# distortion-noise-and-ring-modulator-v1_1.net
KiCad netlist of a schematic drawn in EAGLE
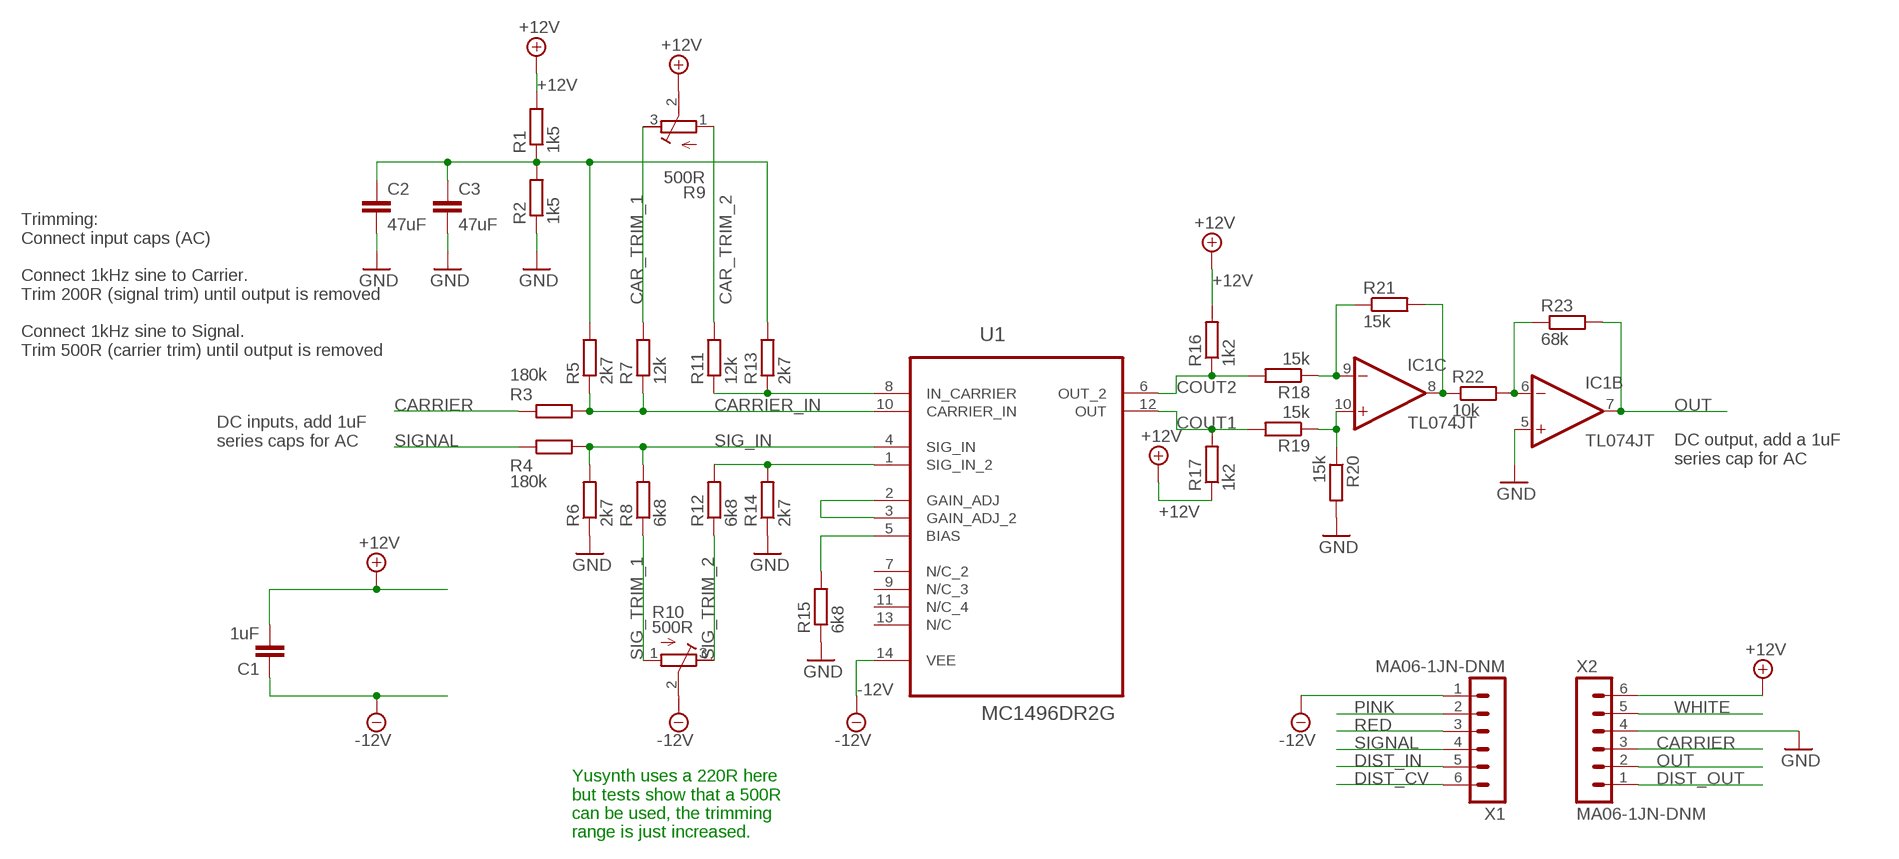
[diagram p0: schematic, sheet 1]
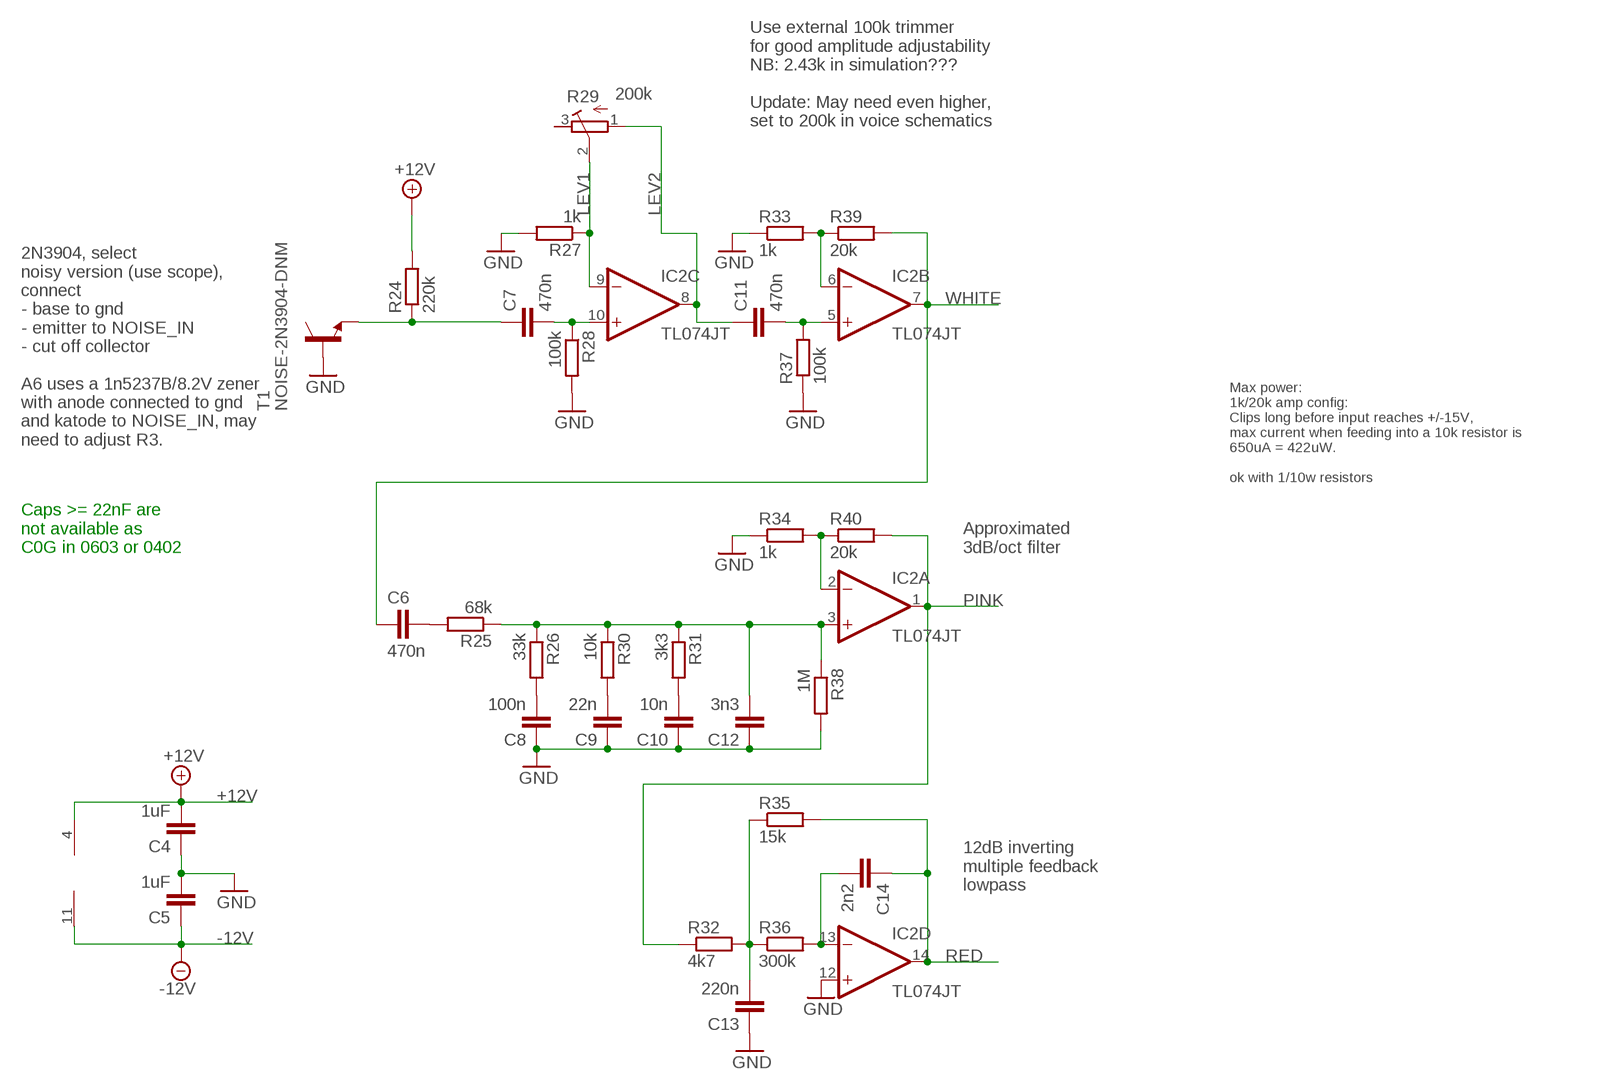
[diagram p1: schematic, sheet 2]
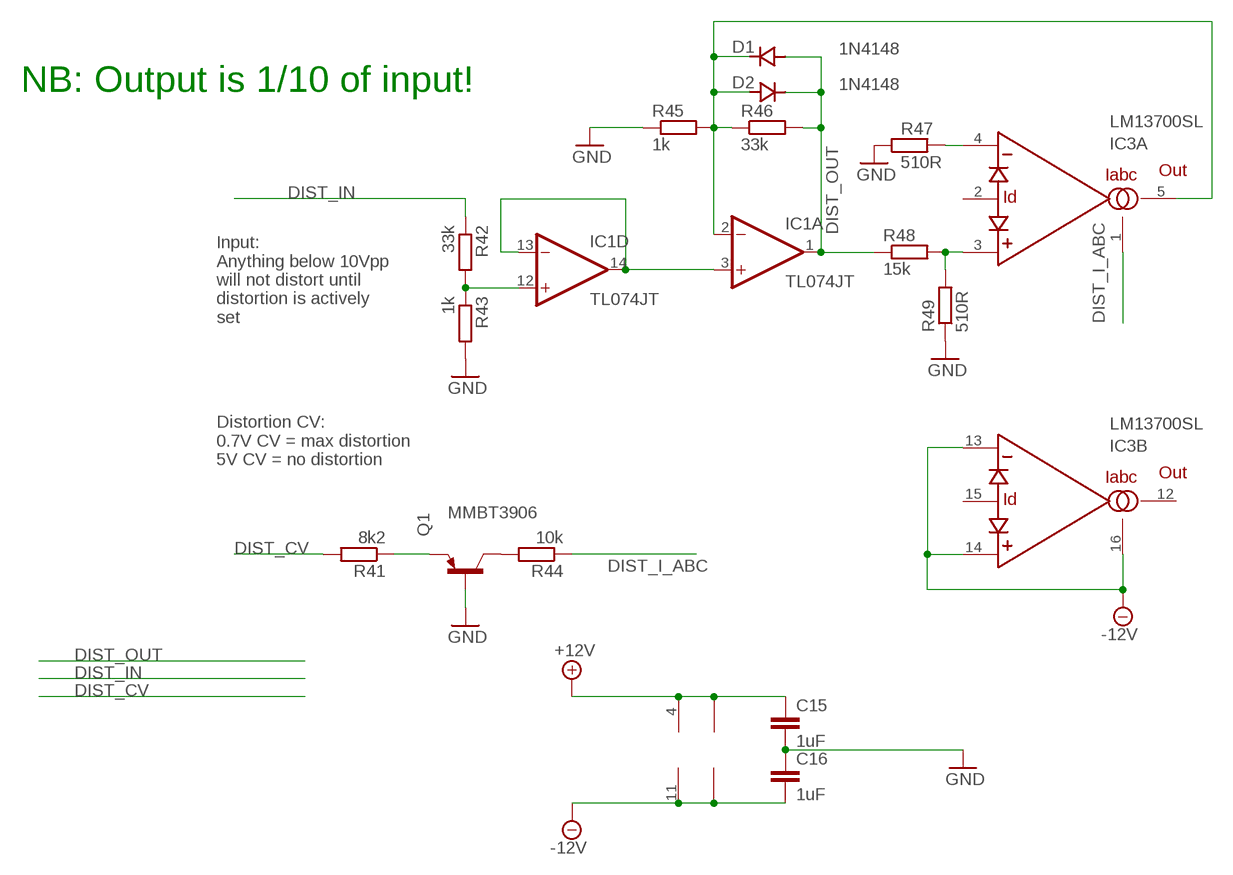
[diagram p2: schematic, sheet 3]

(export (version "E")
  (design (tool "Eeschema 10.0.6"))
  (components
    (comp (ref "C4")
      (value "1uF")
      (footprint "eagle-import:C0402-J")
      (libsource (lib "eagle-import") (part "C-EU-J0402"))
    )
    (comp (ref "C5")
      (value "1uF")
      (footprint "eagle-import:C0402-J")
      (libsource (lib "eagle-import") (part "C-EU-J0402"))
    )
    (comp (ref "C6")
      (value "470n")
      (footprint "eagle-import:C0603-J")
      (libsource (lib "eagle-import") (part "C-EU-J0603"))
    )
    (comp (ref "C7")
      (value "470n")
      (footprint "eagle-import:C0603-J")
      (libsource (lib "eagle-import") (part "C-EU-J0603"))
    )
    (comp (ref "C8")
      (value "100n")
      (footprint "eagle-import:C0402-J")
      (libsource (lib "eagle-import") (part "C-EU-J0402"))
    )
    (comp (ref "C9")
      (value "22n")
      (footprint "eagle-import:C0402-J")
      (libsource (lib "eagle-import") (part "C-EU-J0402"))
    )
    (comp (ref "C10")
      (value "10n")
      (footprint "eagle-import:C0402-J")
      (libsource (lib "eagle-import") (part "C-EU-J0402"))
    )
    (comp (ref "C11")
      (value "470n")
      (footprint "eagle-import:C0603-J")
      (libsource (lib "eagle-import") (part "C-EU-J0603"))
    )
    (comp (ref "C12")
      (value "3n3")
      (footprint "eagle-import:C0603-J")
      (libsource (lib "eagle-import") (part "C-EU-J0603"))
    )
    (comp (ref "C13")
      (value "220n")
      (footprint "eagle-import:C0402-J")
      (libsource (lib "eagle-import") (part "C-EU-J0402"))
    )
    (comp (ref "C14")
      (value "2n2")
      (footprint "eagle-import:C0603-J")
      (libsource (lib "eagle-import") (part "C-EU-J0603"))
    )
    (comp (ref "IC2")
      (value "TL074JT")
      (footprint "eagle-import:TSSOP14J")
      (libsource (lib "eagle-import") (part "TL074JT"))
    )
    (comp (ref "R24")
      (value "220k")
      (footprint "eagle-import:R0603")
      (libsource (lib "eagle-import") (part "R-EU_R0603"))
    )
    (comp (ref "R25")
      (value "68k")
      (footprint "eagle-import:R0603")
      (libsource (lib "eagle-import") (part "R-EU_R0603"))
    )
    (comp (ref "R26")
      (value "33k")
      (footprint "eagle-import:R0402")
      (libsource (lib "eagle-import") (part "R-EU_R0402"))
    )
    (comp (ref "R27")
      (value "1k")
      (footprint "eagle-import:R0402")
      (libsource (lib "eagle-import") (part "R-EU_R0402"))
    )
    (comp (ref "R28")
      (value "100k")
      (footprint "eagle-import:R0402")
      (libsource (lib "eagle-import") (part "R-EU_R0402"))
    )
    (comp (ref "R29")
      (value "200k")
      (footprint "eagle-import:RTRIM3296W")
      (libsource (lib "eagle-import") (part "R-TRIMM3296W"))
    )
    (comp (ref "R30")
      (value "10k")
      (footprint "eagle-import:R0402")
      (libsource (lib "eagle-import") (part "R-EU_R0402"))
    )
    (comp (ref "R31")
      (value "3k3")
      (footprint "eagle-import:R0402")
      (libsource (lib "eagle-import") (part "R-EU_R0402"))
    )
    (comp (ref "R32")
      (value "4k7")
      (footprint "eagle-import:R0402")
      (libsource (lib "eagle-import") (part "R-EU_R0402"))
    )
    (comp (ref "R33")
      (value "1k")
      (footprint "eagle-import:R0402")
      (libsource (lib "eagle-import") (part "R-EU_R0402"))
    )
    (comp (ref "R34")
      (value "1k")
      (footprint "eagle-import:R0402")
      (libsource (lib "eagle-import") (part "R-EU_R0402"))
    )
    (comp (ref "R35")
      (value "15k")
      (footprint "eagle-import:R0402")
      (libsource (lib "eagle-import") (part "R-EU_R0402"))
    )
    (comp (ref "R36")
      (value "300k")
      (footprint "eagle-import:R0603")
      (libsource (lib "eagle-import") (part "R-EU_R0603"))
    )
    (comp (ref "R37")
      (value "100k")
      (footprint "eagle-import:R0402")
      (libsource (lib "eagle-import") (part "R-EU_R0402"))
    )
    (comp (ref "R38")
      (value "1M")
      (footprint "eagle-import:R0402")
      (libsource (lib "eagle-import") (part "R-EU_R0402"))
    )
    (comp (ref "R39")
      (value "20k")
      (footprint "eagle-import:R0402")
      (libsource (lib "eagle-import") (part "R-EU_R0402"))
    )
    (comp (ref "R40")
      (value "20k")
      (footprint "eagle-import:R0402")
      (libsource (lib "eagle-import") (part "R-EU_R0402"))
    )
    (comp (ref "T1")
      (value "NOISE-2N3904-DNM")
      (footprint "eagle-import:NOISE-2N3904-J")
      (libsource (lib "eagle-import") (part "NOISE-2N3904"))
    )
    (comp (ref "C1")
      (value "1uF")
      (footprint "eagle-import:C0402-J")
      (libsource (lib "eagle-import") (part "C-EU-J0402"))
    )
    (comp (ref "C2")
      (value "47uF")
      (footprint "eagle-import:C1206")
      (libsource (lib "eagle-import") (part "C-EUC1206"))
    )
    (comp (ref "C3")
      (value "47uF")
      (footprint "eagle-import:C1206")
      (libsource (lib "eagle-import") (part "C-EUC1206"))
    )
    (comp (ref "IC1")
      (value "TL074JT")
      (footprint "eagle-import:TSSOP14J")
      (libsource (lib "eagle-import") (part "TL074JT"))
    )
    (comp (ref "R1")
      (value "1k5")
      (footprint "eagle-import:R0402")
      (libsource (lib "eagle-import") (part "R-EU_R0402"))
    )
    (comp (ref "R2")
      (value "1k5")
      (footprint "eagle-import:R0402")
      (libsource (lib "eagle-import") (part "R-EU_R0402"))
    )
    (comp (ref "R3")
      (value "180k")
      (footprint "eagle-import:R0402")
      (libsource (lib "eagle-import") (part "R-EU_R0402"))
    )
    (comp (ref "R4")
      (value "180k")
      (footprint "eagle-import:R0402")
      (libsource (lib "eagle-import") (part "R-EU_R0402"))
    )
    (comp (ref "R5")
      (value "2k7")
      (footprint "eagle-import:R0603")
      (libsource (lib "eagle-import") (part "R-EU_R0603"))
    )
    (comp (ref "R6")
      (value "2k7")
      (footprint "eagle-import:R0603")
      (libsource (lib "eagle-import") (part "R-EU_R0603"))
    )
    (comp (ref "R7")
      (value "12k")
      (footprint "eagle-import:R0402")
      (libsource (lib "eagle-import") (part "R-EU_R0402"))
    )
    (comp (ref "R8")
      (value "6k8")
      (footprint "eagle-import:R0603")
      (libsource (lib "eagle-import") (part "R-EU_R0603"))
    )
    (comp (ref "R9")
      (value "500R")
      (footprint "eagle-import:RTRIM3296X")
      (libsource (lib "eagle-import") (part "R-TRIMM3296X"))
    )
    (comp (ref "R10")
      (value "500R")
      (footprint "eagle-import:RTRIM3296X")
      (libsource (lib "eagle-import") (part "R-TRIMM3296X"))
    )
    (comp (ref "R11")
      (value "12k")
      (footprint "eagle-import:R0402")
      (libsource (lib "eagle-import") (part "R-EU_R0402"))
    )
    (comp (ref "R12")
      (value "6k8")
      (footprint "eagle-import:R0603")
      (libsource (lib "eagle-import") (part "R-EU_R0603"))
    )
    (comp (ref "R13")
      (value "2k7")
      (footprint "eagle-import:R0603")
      (libsource (lib "eagle-import") (part "R-EU_R0603"))
    )
    (comp (ref "R14")
      (value "2k7")
      (footprint "eagle-import:R0603")
      (libsource (lib "eagle-import") (part "R-EU_R0603"))
    )
    (comp (ref "R15")
      (value "6k8")
      (footprint "eagle-import:R0603")
      (libsource (lib "eagle-import") (part "R-EU_R0603"))
    )
    (comp (ref "R16")
      (value "1k2")
      (footprint "eagle-import:R0603")
      (libsource (lib "eagle-import") (part "R-EU_R0603"))
    )
    (comp (ref "R17")
      (value "1k2")
      (footprint "eagle-import:R0603")
      (libsource (lib "eagle-import") (part "R-EU_R0603"))
    )
    (comp (ref "R18")
      (value "15k")
      (footprint "eagle-import:R0402")
      (libsource (lib "eagle-import") (part "R-EU_R0402"))
    )
    (comp (ref "R19")
      (value "15k")
      (footprint "eagle-import:R0402")
      (libsource (lib "eagle-import") (part "R-EU_R0402"))
    )
    (comp (ref "R20")
      (value "15k")
      (footprint "eagle-import:R0402")
      (libsource (lib "eagle-import") (part "R-EU_R0402"))
    )
    (comp (ref "R21")
      (value "15k")
      (footprint "eagle-import:R0402")
      (libsource (lib "eagle-import") (part "R-EU_R0402"))
    )
    (comp (ref "R22")
      (value "10k")
      (footprint "eagle-import:R0402")
      (libsource (lib "eagle-import") (part "R-EU_R0402"))
    )
    (comp (ref "R23")
      (value "68k")
      (footprint "eagle-import:R0603")
      (libsource (lib "eagle-import") (part "R-EU_R0603"))
    )
    (comp (ref "U1")
      (value "MC1496DR2G")
      (footprint "eagle-import:SOIC127P600X175-14N")
      (libsource (lib "eagle-import") (part "MC1496DR2G"))
    )
    (comp (ref "X1")
      (value "MA06-1JN-DNM")
      (footprint "eagle-import:MA06N-1J")
      (libsource (lib "eagle-import") (part "MA06-1JN"))
    )
    (comp (ref "X2")
      (value "MA06-1JN-DNM")
      (footprint "eagle-import:MA06N-1J")
      (libsource (lib "eagle-import") (part "MA06-1JN"))
    )
    (comp (ref "C15")
      (value "1uF")
      (footprint "eagle-import:C0402-J")
      (libsource (lib "eagle-import") (part "C-EU-J0402"))
    )
    (comp (ref "C16")
      (value "1uF")
      (footprint "eagle-import:C0402-J")
      (libsource (lib "eagle-import") (part "C-EU-J0402"))
    )
    (comp (ref "D1")
      (value "1N4148")
      (footprint "eagle-import:SOD323J")
      (libsource (lib "eagle-import") (part "1N4148SOD323"))
    )
    (comp (ref "D2")
      (value "1N4148")
      (footprint "eagle-import:SOD323J")
      (libsource (lib "eagle-import") (part "1N4148SOD323"))
    )
    (comp (ref "IC3")
      (value "LM13700SL")
      (footprint "eagle-import:SO16-NARROW-J")
      (libsource (lib "eagle-import") (part "LM13700SL"))
    )
    (comp (ref "Q1")
      (value "MMBT3906")
      (footprint "eagle-import:SOT23-BEC")
      (libsource (lib "eagle-import") (part "MMBT3906SMDLT1"))
    )
    (comp (ref "R41")
      (value "8k2")
      (footprint "eagle-import:R0603")
      (libsource (lib "eagle-import") (part "R-EU_R0603"))
    )
    (comp (ref "R42")
      (value "33k")
      (footprint "eagle-import:R0402")
      (libsource (lib "eagle-import") (part "R-EU_R0402"))
    )
    (comp (ref "R43")
      (value "1k")
      (footprint "eagle-import:R0402")
      (libsource (lib "eagle-import") (part "R-EU_R0402"))
    )
    (comp (ref "R44")
      (value "10k")
      (footprint "eagle-import:R0402")
      (libsource (lib "eagle-import") (part "R-EU_R0402"))
    )
    (comp (ref "R45")
      (value "1k")
      (footprint "eagle-import:R0402")
      (libsource (lib "eagle-import") (part "R-EU_R0402"))
    )
    (comp (ref "R46")
      (value "33k")
      (footprint "eagle-import:R0402")
      (libsource (lib "eagle-import") (part "R-EU_R0402"))
    )
    (comp (ref "R47")
      (value "510R")
      (footprint "eagle-import:R0402")
      (libsource (lib "eagle-import") (part "R-EU_R0402"))
    )
    (comp (ref "R48")
      (value "15k")
      (footprint "eagle-import:R0402")
      (libsource (lib "eagle-import") (part "R-EU_R0402"))
    )
    (comp (ref "R49")
      (value "510R")
      (footprint "eagle-import:R0402")
      (libsource (lib "eagle-import") (part "R-EU_R0402"))
    )
  )
  (nets
    (net (code "1") (name "+12V") (class "Default")
      (node (ref "C1") (pin "2") (pinfunction "2_2") (pintype "passive"))
      (node (ref "C15") (pin "1") (pinfunction "1_1") (pintype "passive"))
      (node (ref "C4") (pin "2") (pinfunction "2_2") (pintype "passive"))
      (node (ref "IC1") (pin "4") (pinfunction "V+_4") (pintype "power_in"))
      (node (ref "IC2") (pin "4") (pinfunction "V+_4") (pintype "power_in"))
      (node (ref "IC3") (pin "11") (pinfunction "V+_11") (pintype "bidirectional"))
      (node (ref "R1") (pin "2") (pinfunction "2_2") (pintype "passive"))
      (node (ref "R16") (pin "2") (pinfunction "2_2") (pintype "passive"))
      (node (ref "R17") (pin "1") (pinfunction "1_1") (pintype "passive"))
      (node (ref "R24") (pin "2") (pinfunction "2_2") (pintype "passive"))
      (node (ref "R9") (pin "2") (pinfunction "S_2") (pintype "passive"))
      (node (ref "X2") (pin "6") (pinfunction "6_6") (pintype "passive"))
    )
    (net (code "2") (name "-12V") (class "Default")
      (node (ref "C1") (pin "1") (pinfunction "1_1") (pintype "passive"))
      (node (ref "C16") (pin "2") (pinfunction "2_2") (pintype "passive"))
      (node (ref "C5") (pin "1") (pinfunction "1_1") (pintype "passive"))
      (node (ref "IC1") (pin "11") (pinfunction "V-_11") (pintype "power_in"))
      (node (ref "IC2") (pin "11") (pinfunction "V-_11") (pintype "power_in"))
      (node (ref "IC3") (pin "13") (pinfunction "-IN_13") (pintype "bidirectional"))
      (node (ref "IC3") (pin "14") (pinfunction "+IN_14") (pintype "bidirectional"))
      (node (ref "IC3") (pin "16") (pinfunction "IABC_16") (pintype "bidirectional"))
      (node (ref "IC3") (pin "6") (pinfunction "V-_6") (pintype "bidirectional"))
      (node (ref "R10") (pin "2") (pinfunction "S_2") (pintype "passive"))
      (node (ref "U1") (pin "14") (pinfunction "VEE_14") (pintype "passive"))
      (node (ref "X1") (pin "1") (pinfunction "1_1") (pintype "passive"))
    )
    (net (code "3") (name "CARRIER") (class "Default")
      (node (ref "R3") (pin "1") (pinfunction "1_1") (pintype "passive"))
      (node (ref "X2") (pin "3") (pinfunction "3_3") (pintype "passive"))
    )
    (net (code "4") (name "CARRIER_IN") (class "Default")
      (node (ref "R3") (pin "2") (pinfunction "2_2") (pintype "passive"))
      (node (ref "R5") (pin "1") (pinfunction "1_1") (pintype "passive"))
      (node (ref "R7") (pin "1") (pinfunction "1_1") (pintype "passive"))
      (node (ref "U1") (pin "10") (pinfunction "CARRIER_IN_10") (pintype "power_in"))
    )
    (net (code "5") (name "CAR_TRIM_1") (class "Default")
      (node (ref "R7") (pin "2") (pinfunction "2_2") (pintype "passive"))
      (node (ref "R9") (pin "3") (pinfunction "E_3") (pintype "passive"))
    )
    (net (code "6") (name "CAR_TRIM_2") (class "Default")
      (node (ref "R11") (pin "2") (pinfunction "2_2") (pintype "passive"))
      (node (ref "R9") (pin "1") (pinfunction "A_1") (pintype "passive"))
    )
    (net (code "7") (name "COUT1") (class "Default")
      (node (ref "R17") (pin "2") (pinfunction "2_2") (pintype "passive"))
      (node (ref "R19") (pin "2") (pinfunction "2_2") (pintype "passive"))
      (node (ref "U1") (pin "12") (pinfunction "OUT_12") (pintype "output"))
    )
    (net (code "8") (name "COUT2") (class "Default")
      (node (ref "R16") (pin "1") (pinfunction "1_1") (pintype "passive"))
      (node (ref "R18") (pin "2") (pinfunction "2_2") (pintype "passive"))
      (node (ref "U1") (pin "6") (pinfunction "OUT_2_6") (pintype "output"))
    )
    (net (code "9") (name "DIST_CV") (class "Default")
      (node (ref "R41") (pin "2") (pinfunction "2_2") (pintype "passive"))
      (node (ref "X1") (pin "6") (pinfunction "6_6") (pintype "passive"))
    )
    (net (code "10") (name "DIST_IN") (class "Default")
      (node (ref "R42") (pin "1") (pinfunction "1_1") (pintype "passive"))
      (node (ref "X1") (pin "5") (pinfunction "5_5") (pintype "passive"))
    )
    (net (code "11") (name "DIST_I_ABC") (class "Default")
      (node (ref "IC3") (pin "1") (pinfunction "IABC_1") (pintype "bidirectional"))
      (node (ref "R44") (pin "1") (pinfunction "1_1") (pintype "passive"))
    )
    (net (code "12") (name "DIST_OUT") (class "Default")
      (node (ref "D1") (pin "2") (pinfunction "A_2") (pintype "passive"))
      (node (ref "D2") (pin "1") (pinfunction "C_1") (pintype "passive"))
      (node (ref "IC1") (pin "1") (pinfunction "OUT_1") (pintype "output"))
      (node (ref "R46") (pin "2") (pinfunction "2_2") (pintype "passive"))
      (node (ref "R48") (pin "1") (pinfunction "1_1") (pintype "passive"))
      (node (ref "X2") (pin "1") (pinfunction "1_1") (pintype "passive"))
    )
    (net (code "13") (name "GND") (class "Default")
      (node (ref "C10") (pin "1") (pinfunction "1_1") (pintype "passive"))
      (node (ref "C12") (pin "1") (pinfunction "1_1") (pintype "passive"))
      (node (ref "C13") (pin "1") (pinfunction "1_1") (pintype "passive"))
      (node (ref "C15") (pin "2") (pinfunction "2_2") (pintype "passive"))
      (node (ref "C16") (pin "1") (pinfunction "1_1") (pintype "passive"))
      (node (ref "C2") (pin "2") (pinfunction "2_2") (pintype "passive"))
      (node (ref "C3") (pin "2") (pinfunction "2_2") (pintype "passive"))
      (node (ref "C4") (pin "1") (pinfunction "1_1") (pintype "passive"))
      (node (ref "C5") (pin "2") (pinfunction "2_2") (pintype "passive"))
      (node (ref "C8") (pin "1") (pinfunction "1_1") (pintype "passive"))
      (node (ref "C9") (pin "1") (pinfunction "1_1") (pintype "passive"))
      (node (ref "IC1") (pin "5") (pinfunction "+IN_5") (pintype "input"))
      (node (ref "IC2") (pin "12") (pinfunction "+IN_12") (pintype "input"))
      (node (ref "Q1") (pin "B") (pinfunction "B_B") (pintype "passive"))
      (node (ref "R14") (pin "1") (pinfunction "1_1") (pintype "passive"))
      (node (ref "R15") (pin "1") (pinfunction "1_1") (pintype "passive"))
      (node (ref "R2") (pin "1") (pinfunction "1_1") (pintype "passive"))
      (node (ref "R20") (pin "2") (pinfunction "2_2") (pintype "passive"))
      (node (ref "R27") (pin "2") (pinfunction "2_2") (pintype "passive"))
      (node (ref "R28") (pin "2") (pinfunction "2_2") (pintype "passive"))
      (node (ref "R33") (pin "1") (pinfunction "1_1") (pintype "passive"))
      (node (ref "R34") (pin "1") (pinfunction "1_1") (pintype "passive"))
      (node (ref "R37") (pin "1") (pinfunction "1_1") (pintype "passive"))
      (node (ref "R38") (pin "2") (pinfunction "2_2") (pintype "passive"))
      (node (ref "R43") (pin "2") (pinfunction "2_2") (pintype "passive"))
      (node (ref "R45") (pin "1") (pinfunction "1_1") (pintype "passive"))
      (node (ref "R47") (pin "1") (pinfunction "1_1") (pintype "passive"))
      (node (ref "R49") (pin "1") (pinfunction "1_1") (pintype "passive"))
      (node (ref "R6") (pin "1") (pinfunction "1_1") (pintype "passive"))
      (node (ref "T1") (pin "B") (pinfunction "B_B") (pintype "passive"))
      (node (ref "X2") (pin "4") (pinfunction "4_4") (pintype "passive"))
    )
    (net (code "14") (name "LEV1") (class "Default")
      (node (ref "IC2") (pin "9") (pinfunction "-IN_9") (pintype "input"))
      (node (ref "R27") (pin "1") (pinfunction "1_1") (pintype "passive"))
      (node (ref "R29") (pin "2") (pinfunction "S_2") (pintype "passive"))
    )
    (net (code "15") (name "LEV2") (class "Default")
      (node (ref "C11") (pin "1") (pinfunction "1_1") (pintype "passive"))
      (node (ref "IC2") (pin "8") (pinfunction "OUT_8") (pintype "output"))
      (node (ref "R29") (pin "1") (pinfunction "A_1") (pintype "passive"))
    )
    (net (code "16") (name "Net-(C2-Pad1)") (class "Default")
      (node (ref "C2") (pin "1") (pinfunction "1_1") (pintype "passive"))
      (node (ref "C3") (pin "1") (pinfunction "1_1") (pintype "passive"))
      (node (ref "R1") (pin "1") (pinfunction "1_1") (pintype "passive"))
      (node (ref "R13") (pin "2") (pinfunction "2_2") (pintype "passive"))
      (node (ref "R2") (pin "2") (pinfunction "2_2") (pintype "passive"))
      (node (ref "R5") (pin "2") (pinfunction "2_2") (pintype "passive"))
    )
    (net (code "17") (name "Net-(C6-Pad2)") (class "Default")
      (node (ref "C6") (pin "2") (pinfunction "2_2") (pintype "passive"))
      (node (ref "R25") (pin "2") (pinfunction "2_2") (pintype "passive"))
    )
    (net (code "18") (name "Net-(C7-Pad1)") (class "Default")
      (node (ref "C7") (pin "1") (pinfunction "1_1") (pintype "passive"))
      (node (ref "R24") (pin "1") (pinfunction "1_1") (pintype "passive"))
      (node (ref "T1") (pin "E") (pinfunction "E_E") (pintype "passive"))
    )
    (net (code "19") (name "Net-(C8-Pad2)") (class "Default")
      (node (ref "C8") (pin "2") (pinfunction "2_2") (pintype "passive"))
      (node (ref "R26") (pin "2") (pinfunction "2_2") (pintype "passive"))
    )
    (net (code "20") (name "Net-(C9-Pad2)") (class "Default")
      (node (ref "C9") (pin "2") (pinfunction "2_2") (pintype "passive"))
      (node (ref "R30") (pin "2") (pinfunction "2_2") (pintype "passive"))
    )
    (net (code "21") (name "Net-(C10-Pad2)") (class "Default")
      (node (ref "C10") (pin "2") (pinfunction "2_2") (pintype "passive"))
      (node (ref "R31") (pin "2") (pinfunction "2_2") (pintype "passive"))
    )
    (net (code "22") (name "Net-(C13-Pad2)") (class "Default")
      (node (ref "C13") (pin "2") (pinfunction "2_2") (pintype "passive"))
      (node (ref "R32") (pin "2") (pinfunction "2_2") (pintype "passive"))
      (node (ref "R35") (pin "1") (pinfunction "1_1") (pintype "passive"))
      (node (ref "R36") (pin "1") (pinfunction "1_1") (pintype "passive"))
    )
    (net (code "23") (name "Net-(D1-C)") (class "Default")
      (node (ref "D1") (pin "1") (pinfunction "C_1") (pintype "passive"))
      (node (ref "D2") (pin "2") (pinfunction "A_2") (pintype "passive"))
      (node (ref "IC1") (pin "2") (pinfunction "-IN_2") (pintype "input"))
      (node (ref "IC3") (pin "5") (pinfunction "OUT_5") (pintype "bidirectional"))
      (node (ref "R45") (pin "2") (pinfunction "2_2") (pintype "passive"))
      (node (ref "R46") (pin "1") (pinfunction "1_1") (pintype "passive"))
    )
    (net (code "24") (name "Net-(IC1A-+IN)") (class "Default")
      (node (ref "IC1") (pin "13") (pinfunction "-IN_13") (pintype "input"))
      (node (ref "IC1") (pin "14") (pinfunction "OUT_14") (pintype "output"))
      (node (ref "IC1") (pin "3") (pinfunction "+IN_3") (pintype "input"))
    )
    (net (code "25") (name "Net-(IC1B--IN)") (class "Default")
      (node (ref "IC1") (pin "6") (pinfunction "-IN_6") (pintype "input"))
      (node (ref "R22") (pin "2") (pinfunction "2_2") (pintype "passive"))
      (node (ref "R23") (pin "1") (pinfunction "1_1") (pintype "passive"))
    )
    (net (code "26") (name "Net-(IC1C-+IN)") (class "Default")
      (node (ref "IC1") (pin "10") (pinfunction "+IN_10") (pintype "input"))
      (node (ref "R19") (pin "1") (pinfunction "1_1") (pintype "passive"))
      (node (ref "R20") (pin "1") (pinfunction "1_1") (pintype "passive"))
    )
    (net (code "27") (name "Net-(IC1C--IN)") (class "Default")
      (node (ref "IC1") (pin "9") (pinfunction "-IN_9") (pintype "input"))
      (node (ref "R18") (pin "1") (pinfunction "1_1") (pintype "passive"))
      (node (ref "R21") (pin "1") (pinfunction "1_1") (pintype "passive"))
    )
    (net (code "28") (name "Net-(IC1C-OUT)") (class "Default")
      (node (ref "IC1") (pin "8") (pinfunction "OUT_8") (pintype "output"))
      (node (ref "R21") (pin "2") (pinfunction "2_2") (pintype "passive"))
      (node (ref "R22") (pin "1") (pinfunction "1_1") (pintype "passive"))
    )
    (net (code "29") (name "Net-(IC1D-+IN)") (class "Default")
      (node (ref "IC1") (pin "12") (pinfunction "+IN_12") (pintype "input"))
      (node (ref "R42") (pin "2") (pinfunction "2_2") (pintype "passive"))
      (node (ref "R43") (pin "1") (pinfunction "1_1") (pintype "passive"))
    )
    (net (code "30") (name "Net-(IC2A-+IN)") (class "Default")
      (node (ref "C12") (pin "2") (pinfunction "2_2") (pintype "passive"))
      (node (ref "IC2") (pin "3") (pinfunction "+IN_3") (pintype "input"))
      (node (ref "R25") (pin "1") (pinfunction "1_1") (pintype "passive"))
      (node (ref "R26") (pin "1") (pinfunction "1_1") (pintype "passive"))
      (node (ref "R30") (pin "1") (pinfunction "1_1") (pintype "passive"))
      (node (ref "R31") (pin "1") (pinfunction "1_1") (pintype "passive"))
      (node (ref "R38") (pin "1") (pinfunction "1_1") (pintype "passive"))
    )
    (net (code "31") (name "Net-(IC2A--IN)") (class "Default")
      (node (ref "IC2") (pin "2") (pinfunction "-IN_2") (pintype "input"))
      (node (ref "R34") (pin "2") (pinfunction "2_2") (pintype "passive"))
      (node (ref "R40") (pin "1") (pinfunction "1_1") (pintype "passive"))
    )
    (net (code "32") (name "Net-(IC2B-+IN)") (class "Default")
      (node (ref "C11") (pin "2") (pinfunction "2_2") (pintype "passive"))
      (node (ref "IC2") (pin "5") (pinfunction "+IN_5") (pintype "input"))
      (node (ref "R37") (pin "2") (pinfunction "2_2") (pintype "passive"))
    )
    (net (code "33") (name "Net-(IC2B--IN)") (class "Default")
      (node (ref "IC2") (pin "6") (pinfunction "-IN_6") (pintype "input"))
      (node (ref "R33") (pin "2") (pinfunction "2_2") (pintype "passive"))
      (node (ref "R39") (pin "1") (pinfunction "1_1") (pintype "passive"))
    )
    (net (code "34") (name "Net-(IC2C-+IN)") (class "Default")
      (node (ref "C7") (pin "2") (pinfunction "2_2") (pintype "passive"))
      (node (ref "IC2") (pin "10") (pinfunction "+IN_10") (pintype "input"))
      (node (ref "R28") (pin "1") (pinfunction "1_1") (pintype "passive"))
    )
    (net (code "35") (name "Net-(IC2D--IN)") (class "Default")
      (node (ref "C14") (pin "2") (pinfunction "2_2") (pintype "passive"))
      (node (ref "IC2") (pin "13") (pinfunction "-IN_13") (pintype "input"))
      (node (ref "R36") (pin "2") (pinfunction "2_2") (pintype "passive"))
    )
    (net (code "36") (name "Net-(IC3A-+IN)") (class "Default")
      (node (ref "IC3") (pin "3") (pinfunction "+IN_3") (pintype "bidirectional"))
      (node (ref "R48") (pin "2") (pinfunction "2_2") (pintype "passive"))
      (node (ref "R49") (pin "2") (pinfunction "2_2") (pintype "passive"))
    )
    (net (code "37") (name "Net-(IC3A--IN)") (class "Default")
      (node (ref "IC3") (pin "4") (pinfunction "-IN_4") (pintype "bidirectional"))
      (node (ref "R47") (pin "2") (pinfunction "2_2") (pintype "passive"))
    )
    (net (code "38") (name "Net-(Q1-PadC)") (class "Default")
      (node (ref "Q1") (pin "C") (pinfunction "C_C") (pintype "passive"))
      (node (ref "R44") (pin "2") (pinfunction "2_2") (pintype "passive"))
    )
    (net (code "39") (name "Net-(Q1-PadE)") (class "Default")
      (node (ref "Q1") (pin "E") (pinfunction "E_E") (pintype "passive"))
      (node (ref "R41") (pin "1") (pinfunction "1_1") (pintype "passive"))
    )
    (net (code "40") (name "Net-(U1-BIAS)") (class "Default")
      (node (ref "R15") (pin "2") (pinfunction "2_2") (pintype "passive"))
      (node (ref "U1") (pin "5") (pinfunction "BIAS_5") (pintype "input"))
    )
    (net (code "41") (name "Net-(U1-GAIN_ADJ)") (class "Default")
      (node (ref "U1") (pin "2") (pinfunction "GAIN_ADJ_2") (pintype "input"))
      (node (ref "U1") (pin "3") (pinfunction "GAIN_ADJ_2_3") (pintype "input"))
    )
    (net (code "42") (name "Net-(U1-IN_CARRIER)") (class "Default")
      (node (ref "R11") (pin "1") (pinfunction "1_1") (pintype "passive"))
      (node (ref "R13") (pin "1") (pinfunction "1_1") (pintype "passive"))
      (node (ref "U1") (pin "8") (pinfunction "IN_CARRIER_8") (pintype "power_in"))
    )
    (net (code "43") (name "Net-(U1-SIG_IN_2)") (class "Default")
      (node (ref "R12") (pin "2") (pinfunction "2_2") (pintype "passive"))
      (node (ref "R14") (pin "2") (pinfunction "2_2") (pintype "passive"))
      (node (ref "U1") (pin "1") (pinfunction "SIG_IN_2_1") (pintype "input"))
    )
    (net (code "44") (name "OUT") (class "Default")
      (node (ref "IC1") (pin "7") (pinfunction "OUT_7") (pintype "output"))
      (node (ref "R23") (pin "2") (pinfunction "2_2") (pintype "passive"))
      (node (ref "X2") (pin "2") (pinfunction "2_2") (pintype "passive"))
    )
    (net (code "45") (name "PINK") (class "Default")
      (node (ref "IC2") (pin "1") (pinfunction "OUT_1") (pintype "output"))
      (node (ref "R32") (pin "1") (pinfunction "1_1") (pintype "passive"))
      (node (ref "R40") (pin "2") (pinfunction "2_2") (pintype "passive"))
      (node (ref "X1") (pin "2") (pinfunction "2_2") (pintype "passive"))
    )
    (net (code "46") (name "RED") (class "Default")
      (node (ref "C14") (pin "1") (pinfunction "1_1") (pintype "passive"))
      (node (ref "IC2") (pin "14") (pinfunction "OUT_14") (pintype "output"))
      (node (ref "R35") (pin "2") (pinfunction "2_2") (pintype "passive"))
      (node (ref "X1") (pin "3") (pinfunction "3_3") (pintype "passive"))
    )
    (net (code "47") (name "SIGNAL") (class "Default")
      (node (ref "R4") (pin "1") (pinfunction "1_1") (pintype "passive"))
      (node (ref "X1") (pin "4") (pinfunction "4_4") (pintype "passive"))
    )
    (net (code "48") (name "SIG_IN") (class "Default")
      (node (ref "R4") (pin "2") (pinfunction "2_2") (pintype "passive"))
      (node (ref "R6") (pin "2") (pinfunction "2_2") (pintype "passive"))
      (node (ref "R8") (pin "2") (pinfunction "2_2") (pintype "passive"))
      (node (ref "U1") (pin "4") (pinfunction "SIG_IN_4") (pintype "input"))
    )
    (net (code "49") (name "SIG_TRIM_1") (class "Default")
      (node (ref "R10") (pin "1") (pinfunction "A_1") (pintype "passive"))
      (node (ref "R8") (pin "1") (pinfunction "1_1") (pintype "passive"))
    )
    (net (code "50") (name "SIG_TRIM_2") (class "Default")
      (node (ref "R10") (pin "3") (pinfunction "E_3") (pintype "passive"))
      (node (ref "R12") (pin "1") (pinfunction "1_1") (pintype "passive"))
    )
    (net (code "51") (name "WHITE") (class "Default")
      (node (ref "C6") (pin "1") (pinfunction "1_1") (pintype "passive"))
      (node (ref "IC2") (pin "7") (pinfunction "OUT_7") (pintype "output"))
      (node (ref "R39") (pin "2") (pinfunction "2_2") (pintype "passive"))
      (node (ref "X2") (pin "5") (pinfunction "5_5") (pintype "passive"))
    )
    (net (code "52") (name "unconnected-(IC3A-ID-Pad2)") (class "Default")
      (node (ref "IC3") (pin "2") (pinfunction "ID_2") (pintype "bidirectional"))
    )
    (net (code "53") (name "unconnected-(IC3B-ID-Pad15)") (class "Default")
      (node (ref "IC3") (pin "15") (pinfunction "ID_15") (pintype "bidirectional"))
    )
    (net (code "54") (name "unconnected-(IC3B-OUT-Pad12)") (class "Default")
      (node (ref "IC3") (pin "12") (pinfunction "OUT_12") (pintype "bidirectional"))
    )
    (net (code "55") (name "unconnected-(R29-E-Pad3)") (class "Default")
      (node (ref "R29") (pin "3") (pinfunction "E_3") (pintype "passive"))
    )
    (net (code "56") (name "unconnected-(U1-N{slash}C-Pad13)") (class "Default")
      (node (ref "U1") (pin "13") (pinfunction "N/C_13") (pintype "no_connect"))
    )
    (net (code "57") (name "unconnected-(U1-N{slash}C_2-Pad7)") (class "Default")
      (node (ref "U1") (pin "7") (pinfunction "N/C_2_7") (pintype "no_connect"))
    )
    (net (code "58") (name "unconnected-(U1-N{slash}C_3-Pad9)") (class "Default")
      (node (ref "U1") (pin "9") (pinfunction "N/C_3_9") (pintype "no_connect"))
    )
    (net (code "59") (name "unconnected-(U1-N{slash}C_4-Pad11)") (class "Default")
      (node (ref "U1") (pin "11") (pinfunction "N/C_4_11") (pintype "no_connect"))
    )
  )
)
